# WattmeterV1_1.net
KiCad netlist of a schematic drawn in Altium Designer
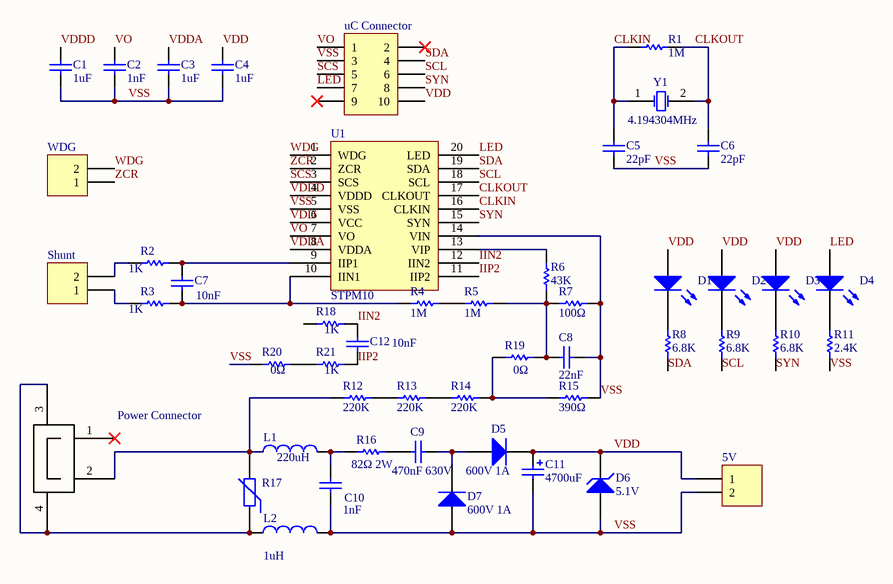
[diagram p0: WattmeterV1.1.SchDoc]

(export (version "E")
  (design (tool "Eeschema 10.0.6"))
  (components
    (comp (ref "5V")
      (value "Header 2")
      (footprint "Female header 2x1")
      (description "Header, 2-Pin")
      (fields (field (name "PUBLISHER") "Altium Limited"))
      (libsource (lib "") (part "Header 2_1"))
    )
    (comp (ref "C1")
      (value "1uF")
      (footprint "Cap SMD 0603")
      (description "Capacitor")
      (fields (field (name "Comment") "Cap") (field (name "PUBLISHER") "Altium Limited"))
      (libsource (lib "Miscellaneous Devices") (part "Cap"))
    )
    (comp (ref "C2")
      (value "1nF")
      (footprint "Cap SMD 0603")
      (description "Capacitor")
      (fields (field (name "Comment") "Cap") (field (name "PUBLISHER") "Altium Limited"))
      (libsource (lib "Miscellaneous Devices") (part "Cap"))
    )
    (comp (ref "C3")
      (value "1uF")
      (footprint "Cap SMD 0603")
      (description "Capacitor")
      (fields (field (name "Comment") "Cap") (field (name "PUBLISHER") "Altium Limited"))
      (libsource (lib "Miscellaneous Devices") (part "Cap"))
    )
    (comp (ref "C4")
      (value "1uF")
      (footprint "Cap SMD 0603")
      (description "Capacitor")
      (fields (field (name "Comment") "Cap") (field (name "PUBLISHER") "Altium Limited"))
      (libsource (lib "Miscellaneous Devices") (part "Cap"))
    )
    (comp (ref "C5")
      (value "22pF")
      (footprint "Cap SMD 0603")
      (description "Capacitor")
      (fields (field (name "Comment") "Cap") (field (name "PUBLISHER") "Altium Limited"))
      (libsource (lib "Miscellaneous Devices") (part "Cap"))
    )
    (comp (ref "C6")
      (value "22pF")
      (footprint "Cap SMD 0603")
      (description "Capacitor")
      (fields (field (name "Comment") "Cap") (field (name "PUBLISHER") "Altium Limited"))
      (libsource (lib "Miscellaneous Devices") (part "Cap"))
    )
    (comp (ref "C7")
      (value "10nF")
      (footprint "Cap SMD 0603")
      (description "Capacitor")
      (fields (field (name "Comment") "Cap") (field (name "PUBLISHER") "Altium Limited"))
      (libsource (lib "Miscellaneous Devices") (part "Cap"))
    )
    (comp (ref "C8")
      (value "22nF")
      (footprint "Cap SMD 0603")
      (description "Capacitor")
      (fields (field (name "Comment") "Cap") (field (name "PUBLISHER") "Altium Limited"))
      (libsource (lib "Miscellaneous Devices") (part "Cap"))
    )
    (comp (ref "C9")
      (value "470nF 630V")
      (footprint "Cap Tenta MKP 470nF X2")
      (description "Capacitor")
      (fields (field (name "Comment") "Cap") (field (name "PUBLISHER") "Altium Limited"))
      (libsource (lib "Miscellaneous Devices") (part "Cap"))
    )
    (comp (ref "C10")
      (value "1nF")
      (footprint "Cap SMD 0603")
      (description "Capacitor")
      (fields (field (name "Comment") "Cap") (field (name "PUBLISHER") "Altium Limited"))
      (libsource (lib "Miscellaneous Devices") (part "Cap"))
    )
    (comp (ref "C11")
      (value "4700uF")
      (footprint "Cap Pol")
      (description "Polarized Capacitor (Axial)")
      (fields (field (name "Comment") "Cap Pol2") (field (name "PUBLISHER") "Altium Limited"))
      (libsource (lib "Miscellaneous Devices") (part "Cap Pol2"))
    )
    (comp (ref "C12")
      (value "10nF")
      (footprint "Cap SMD 0603")
      (description "Capacitor")
      (fields (field (name "Comment") "Cap") (field (name "PUBLISHER") "Altium Limited"))
      (libsource (lib "Miscellaneous Devices") (part "Cap"))
    )
    (comp (ref "D1")
      (value "LED1")
      (footprint "LED Green")
      (description "Typical RED GaAs LED")
      (fields (field (name "PUBLISHER") "Altium Limited"))
      (libsource (lib "Miscellaneous Devices") (part "LED1"))
    )
    (comp (ref "D2")
      (value "LED1")
      (footprint "LED Green")
      (description "Typical RED GaAs LED")
      (fields (field (name "PUBLISHER") "Altium Limited"))
      (libsource (lib "Miscellaneous Devices") (part "LED1"))
    )
    (comp (ref "D3")
      (value "LED1")
      (footprint "LED Green")
      (description "Typical RED GaAs LED")
      (fields (field (name "PUBLISHER") "Altium Limited"))
      (libsource (lib "Miscellaneous Devices") (part "LED1"))
    )
    (comp (ref "D4")
      (value "LED1")
      (footprint "LED Green")
      (description "Typical RED GaAs LED")
      (fields (field (name "PUBLISHER") "Altium Limited"))
      (libsource (lib "Miscellaneous Devices") (part "LED1"))
    )
    (comp (ref "D5")
      (value "600V 1A")
      (footprint "Diode SMD")
      (description "High Conductance Fast Diode")
      (fields (field (name "PUBLISHER") "Altium Limited"))
      (libsource (lib "Miscellaneous Devices") (part "Diode 1N4448"))
    )
    (comp (ref "D6")
      (value "5.1V")
      (footprint "Diode SMD")
      (description "Zener Diode")
      (fields (field (name "PUBLISHER") "Altium Limited"))
      (libsource (lib "Miscellaneous Devices") (part "D Zener"))
    )
    (comp (ref "D7")
      (value "600V 1A")
      (footprint "Diode SMD")
      (description "High Conductance Fast Diode")
      (fields (field (name "PUBLISHER") "Altium Limited"))
      (libsource (lib "Miscellaneous Devices") (part "Diode 1N4448"))
    )
    (comp (ref "L1")
      (value "220uH")
      (footprint "Inductor SMD")
      (description "Inductor")
      (fields (field (name "PUBLISHER") "Altium Limited"))
      (libsource (lib "Miscellaneous Devices") (part "Inductor"))
    )
    (comp (ref "L2")
      (value "1uH")
      (footprint "Inductor SMD")
      (description "Inductor")
      (fields (field (name "PUBLISHER") "Altium Limited"))
      (libsource (lib "Miscellaneous Devices") (part "Inductor"))
    )
    (comp (ref "Power Connector")
      (value "Shunt Resistor")
      (footprint "Power Connector+ Shunt")
      (libsource (lib "STMP Lib") (part "Shunt Resistor"))
    )
    (comp (ref "R1")
      (value "1M")
      (footprint "res 0102")
      (description "Resistor")
      (fields (field (name "Comment") "Res1") (field (name "PUBLISHER") "Altium Limited"))
      (libsource (lib "Miscellaneous Devices") (part "Res1"))
    )
    (comp (ref "R2")
      (value "1K")
      (footprint "Res 0102")
      (description "Resistor")
      (fields (field (name "Comment") "Res1") (field (name "PUBLISHER") "Altium Limited"))
      (libsource (lib "Miscellaneous Devices") (part "Res1"))
    )
    (comp (ref "R3")
      (value "1K")
      (footprint "Res 0102")
      (description "Resistor")
      (fields (field (name "Comment") "Res1") (field (name "PUBLISHER") "Altium Limited"))
      (libsource (lib "Miscellaneous Devices") (part "Res1"))
    )
    (comp (ref "R4")
      (value "1M")
      (footprint "res 0102")
      (description "Resistor")
      (fields (field (name "Comment") "Res1") (field (name "PUBLISHER") "Altium Limited"))
      (libsource (lib "Miscellaneous Devices") (part "Res1"))
    )
    (comp (ref "R5")
      (value "1M")
      (footprint "res 0102")
      (description "Resistor")
      (fields (field (name "Comment") "Res1") (field (name "PUBLISHER") "Altium Limited"))
      (libsource (lib "Miscellaneous Devices") (part "Res1"))
    )
    (comp (ref "R6")
      (value "43K")
      (footprint "res 0102")
      (description "Resistor")
      (fields (field (name "Comment") "Res1") (field (name "PUBLISHER") "Altium Limited"))
      (libsource (lib "Miscellaneous Devices") (part "Res1"))
    )
    (comp (ref "R7")
      (value "100Ω")
      (footprint "res 0102")
      (description "Resistor")
      (fields (field (name "Comment") "Res1") (field (name "PUBLISHER") "Altium Limited"))
      (libsource (lib "Miscellaneous Devices") (part "Res1"))
    )
    (comp (ref "R8")
      (value "6.8K")
      (footprint "RES SMD 0603")
      (description "Resistor")
      (fields (field (name "Comment") "Res1") (field (name "PUBLISHER") "Altium Limited"))
      (libsource (lib "Miscellaneous Devices") (part "Res1"))
    )
    (comp (ref "R9")
      (value "6.8K")
      (footprint "RES SMD 0603")
      (description "Resistor")
      (fields (field (name "Comment") "Res1") (field (name "PUBLISHER") "Altium Limited"))
      (libsource (lib "Miscellaneous Devices") (part "Res1"))
    )
    (comp (ref "R10")
      (value "6.8K")
      (footprint "RES SMD 0603")
      (description "Resistor")
      (fields (field (name "Comment") "Res1") (field (name "PUBLISHER") "Altium Limited"))
      (libsource (lib "Miscellaneous Devices") (part "Res1"))
    )
    (comp (ref "R11")
      (value "2.4K")
      (footprint "RES SMD 0603")
      (description "Resistor")
      (fields (field (name "Comment") "Res1") (field (name "PUBLISHER") "Altium Limited"))
      (libsource (lib "Miscellaneous Devices") (part "Res1"))
    )
    (comp (ref "R12")
      (value "220K")
      (footprint "Res Vertical")
      (description "Resistor")
      (fields (field (name "Comment") "Res1") (field (name "PUBLISHER") "Altium Limited"))
      (libsource (lib "Miscellaneous Devices") (part "Res1"))
    )
    (comp (ref "R13")
      (value "220K")
      (footprint "Res Vertical")
      (description "Resistor")
      (fields (field (name "Comment") "Res1") (field (name "PUBLISHER") "Altium Limited"))
      (libsource (lib "Miscellaneous Devices") (part "Res1"))
    )
    (comp (ref "R14")
      (value "220K")
      (footprint "Res Vertical")
      (description "Resistor")
      (fields (field (name "Comment") "Res1") (field (name "PUBLISHER") "Altium Limited"))
      (libsource (lib "Miscellaneous Devices") (part "Res1"))
    )
    (comp (ref "R15")
      (value "390Ω")
      (footprint "Res 0102")
      (description "Resistor")
      (fields (field (name "Comment") "Res1") (field (name "PUBLISHER") "Altium Limited"))
      (libsource (lib "Miscellaneous Devices") (part "Res1"))
    )
    (comp (ref "R16")
      (value "82Ω 2W")
      (footprint "Res 0.7in")
      (description "Resistor")
      (fields (field (name "Comment") "Res1") (field (name "PUBLISHER") "Altium Limited"))
      (libsource (lib "Miscellaneous Devices") (part "Res1"))
    )
    (comp (ref "R17")
      (value "Res Varistor")
      (footprint "Varistor")
      (description "Varistor (Voltage-Sensitive Resistor)")
      (fields (field (name "PUBLISHER") "Altium Limited"))
      (libsource (lib "Miscellaneous Devices") (part "Res Varistor"))
    )
    (comp (ref "R18")
      (value "1K")
      (footprint "Res SMD 0102")
      (description "Resistor")
      (fields (field (name "Comment") "Res1") (field (name "PUBLISHER") "Altium Limited"))
      (libsource (lib "Miscellaneous Devices") (part "Res1"))
    )
    (comp (ref "R19")
      (value "0Ω")
      (footprint "RES SMD 0603")
      (description "Resistor")
      (fields (field (name "Comment") "Res1") (field (name "PUBLISHER") "Altium Limited"))
      (libsource (lib "Miscellaneous Devices") (part "Res1"))
    )
    (comp (ref "R20")
      (value "0Ω")
      (footprint "RES SMD 0603")
      (description "Resistor")
      (fields (field (name "Comment") "Res1") (field (name "PUBLISHER") "Altium Limited"))
      (libsource (lib "Miscellaneous Devices") (part "Res1"))
    )
    (comp (ref "R21")
      (value "1K")
      (footprint "Res SMD 0102")
      (description "Resistor")
      (fields (field (name "Comment") "Res1") (field (name "PUBLISHER") "Altium Limited"))
      (libsource (lib "Miscellaneous Devices") (part "Res1"))
    )
    (comp (ref "Shunt")
      (value "Header 2")
      (footprint "HDR1X2")
      (description "Header, 2-Pin")
      (fields (field (name "PUBLISHER") "Altium Limited"))
      (libsource (lib "Miscellaneous Connectors") (part "Header 2"))
    )
    (comp (ref "U1") (value "STPM10") (footprint "STPM10") (libsource (lib "STMP Lib") (part "STPM10")))
    (comp (ref "uC Connector")
      (value "Header 5X2")
      (footprint "Male Header 2x5")
      (description "Header, 5-Pin, Dual row")
      (fields (field (name "PUBLISHER") "Altium Limited"))
      (libsource (lib "Miscellaneous Connectors") (part "Header 5X2"))
    )
    (comp (ref "WDG")
      (value "Header 2")
      (footprint "Female header 2x1")
      (description "Header, 2-Pin")
      (fields (field (name "PUBLISHER") "Altium Limited"))
      (libsource (lib "Miscellaneous Connectors") (part "Header 2"))
    )
    (comp (ref "Y1")
      (value "4.194304MHz")
      (footprint "Xtal")
      (description "Crystal Oscillator")
      (fields (field (name "PUBLISHER") "Altium Limited"))
      (libsource (lib "Miscellaneous Devices") (part "XTAL"))
    )
  )
  (nets
    (net (code "1") (name "/CLKIN") (class "Default")
      (node (ref "C5") (pin "2") (pinfunction "2_2") (pintype "passive"))
      (node (ref "R1") (pin "1") (pinfunction "1_1") (pintype "passive"))
      (node (ref "U1") (pin "16") (pinfunction "CLKIN_16") (pintype "passive"))
      (node (ref "Y1") (pin "1") (pinfunction "OSC1_1") (pintype "passive"))
    )
    (net (code "2") (name "/CLKOUT") (class "Default")
      (node (ref "C6") (pin "2") (pinfunction "2_2") (pintype "passive"))
      (node (ref "R1") (pin "2") (pinfunction "2_2") (pintype "passive"))
      (node (ref "U1") (pin "17") (pinfunction "CLKOUT_17") (pintype "passive"))
      (node (ref "Y1") (pin "2") (pinfunction "OSC2_2") (pintype "passive"))
    )
    (net (code "3") (name "/IIN2") (class "Default")
      (node (ref "C12") (pin "2") (pinfunction "2_2") (pintype "passive"))
      (node (ref "R18") (pin "2") (pinfunction "2_2") (pintype "passive"))
      (node (ref "U1") (pin "12") (pinfunction "IIN2_12") (pintype "passive"))
    )
    (net (code "4") (name "/IIP2") (class "Default")
      (node (ref "C12") (pin "1") (pinfunction "1_1") (pintype "passive"))
      (node (ref "R21") (pin "2") (pinfunction "2_2") (pintype "passive"))
      (node (ref "U1") (pin "11") (pinfunction "IIP2_11") (pintype "passive"))
    )
    (net (code "5") (name "/LED") (class "Default")
      (node (ref "D4") (pin "1") (pinfunction "A_1") (pintype "passive"))
      (node (ref "U1") (pin "20") (pinfunction "LED_20") (pintype "passive"))
      (node (ref "uC Connector") (pin "7") (pinfunction "7_7") (pintype "passive"))
    )
    (net (code "6") (name "/SCL") (class "Default")
      (node (ref "R9") (pin "1") (pinfunction "1_1") (pintype "passive"))
      (node (ref "U1") (pin "18") (pinfunction "SCL_18") (pintype "passive"))
      (node (ref "uC Connector") (pin "6") (pinfunction "6_6") (pintype "passive"))
    )
    (net (code "7") (name "/SCS") (class "Default")
      (node (ref "U1") (pin "3") (pinfunction "SCS_3") (pintype "passive"))
      (node (ref "uC Connector") (pin "5") (pinfunction "5_5") (pintype "passive"))
    )
    (net (code "8") (name "/SDA") (class "Default")
      (node (ref "R8") (pin "1") (pinfunction "1_1") (pintype "passive"))
      (node (ref "U1") (pin "19") (pinfunction "SDA_19") (pintype "passive"))
      (node (ref "uC Connector") (pin "4") (pinfunction "4_4") (pintype "passive"))
    )
    (net (code "9") (name "/SYN") (class "Default")
      (node (ref "R10") (pin "1") (pinfunction "1_1") (pintype "passive"))
      (node (ref "U1") (pin "15") (pinfunction "SYN_15") (pintype "passive"))
      (node (ref "uC Connector") (pin "8") (pinfunction "8_8") (pintype "passive"))
    )
    (net (code "10") (name "/VDD") (class "Default")
      (node (ref "5V") (pin "1") (pinfunction "1_1") (pintype "passive"))
      (node (ref "C11") (pin "1") (pinfunction "1_1") (pintype "passive"))
      (node (ref "C4") (pin "2") (pinfunction "2_2") (pintype "passive"))
      (node (ref "D1") (pin "1") (pinfunction "A_1") (pintype "passive"))
      (node (ref "D2") (pin "1") (pinfunction "A_1") (pintype "passive"))
      (node (ref "D3") (pin "1") (pinfunction "A_1") (pintype "passive"))
      (node (ref "D5") (pin "2") (pinfunction "K_2") (pintype "passive"))
      (node (ref "D6") (pin "2") (pinfunction "K_2") (pintype "passive"))
      (node (ref "U1") (pin "6") (pinfunction "VCC_6") (pintype "passive"))
      (node (ref "uC Connector") (pin "10") (pinfunction "10_10") (pintype "passive"))
    )
    (net (code "11") (name "/VDDA") (class "Default")
      (node (ref "C3") (pin "2") (pinfunction "2_2") (pintype "passive"))
      (node (ref "U1") (pin "8") (pinfunction "VDDA_8") (pintype "passive"))
    )
    (net (code "12") (name "/VDDD") (class "Default")
      (node (ref "C1") (pin "2") (pinfunction "2_2") (pintype "passive"))
      (node (ref "U1") (pin "4") (pinfunction "VDDD_4") (pintype "passive"))
    )
    (net (code "13") (name "/VO") (class "Default")
      (node (ref "C2") (pin "2") (pinfunction "2_2") (pintype "passive"))
      (node (ref "U1") (pin "7") (pinfunction "VO_7") (pintype "passive"))
      (node (ref "uC Connector") (pin "1") (pinfunction "1_1") (pintype "passive"))
    )
    (net (code "14") (name "/VSS") (class "Default")
      (node (ref "5V") (pin "2") (pinfunction "2_2") (pintype "passive"))
      (node (ref "C1") (pin "1") (pinfunction "1_1") (pintype "passive"))
      (node (ref "C10") (pin "1") (pinfunction "1_1") (pintype "passive"))
      (node (ref "C11") (pin "2") (pinfunction "2_2") (pintype "passive"))
      (node (ref "C2") (pin "1") (pinfunction "1_1") (pintype "passive"))
      (node (ref "C3") (pin "1") (pinfunction "1_1") (pintype "passive"))
      (node (ref "C4") (pin "1") (pinfunction "1_1") (pintype "passive"))
      (node (ref "C5") (pin "1") (pinfunction "1_1") (pintype "passive"))
      (node (ref "C6") (pin "1") (pinfunction "1_1") (pintype "passive"))
      (node (ref "C8") (pin "2") (pinfunction "2_2") (pintype "passive"))
      (node (ref "D6") (pin "1") (pinfunction "A_1") (pintype "passive"))
      (node (ref "D7") (pin "1") (pinfunction "A_1") (pintype "passive"))
      (node (ref "L2") (pin "2") (pinfunction "2_2") (pintype "passive"))
      (node (ref "R11") (pin "1") (pinfunction "1_1") (pintype "passive"))
      (node (ref "R15") (pin "2") (pinfunction "2_2") (pintype "passive"))
      (node (ref "R20") (pin "1") (pinfunction "1_1") (pintype "passive"))
      (node (ref "R7") (pin "2") (pinfunction "2_2") (pintype "passive"))
      (node (ref "U1") (pin "14") (pinfunction "VIN_14") (pintype "passive"))
      (node (ref "U1") (pin "5") (pinfunction "VSS_5") (pintype "passive"))
      (node (ref "uC Connector") (pin "3") (pinfunction "3_3") (pintype "passive"))
    )
    (net (code "15") (name "/WDG") (class "Default")
      (node (ref "U1") (pin "1") (pinfunction "WDG_1") (pintype "passive"))
      (node (ref "WDG") (pin "2") (pinfunction "2_2") (pintype "passive"))
    )
    (net (code "16") (name "/ZCR") (class "Default")
      (node (ref "U1") (pin "2") (pinfunction "ZCR_2") (pintype "passive"))
      (node (ref "WDG") (pin "1") (pinfunction "1_1") (pintype "passive"))
    )
    (net (code "17") (name "Net-(C8-Pad1)") (class "Default")
      (node (ref "C8") (pin "1") (pinfunction "1_1") (pintype "passive"))
      (node (ref "R19") (pin "2") (pinfunction "2_2") (pintype "passive"))
      (node (ref "R5") (pin "2") (pinfunction "2_2") (pintype "passive"))
      (node (ref "R6") (pin "1") (pinfunction "1_1") (pintype "passive"))
      (node (ref "R7") (pin "1") (pinfunction "1_1") (pintype "passive"))
    )
    (net (code "18") (name "Net-(C9-Pad2)") (class "Default")
      (node (ref "C9") (pin "2") (pinfunction "2_2") (pintype "passive"))
      (node (ref "R16") (pin "2") (pinfunction "2_2") (pintype "passive"))
    )
    (net (code "19") (name "Net-(C10-Pad2)") (class "Default")
      (node (ref "C10") (pin "2") (pinfunction "2_2") (pintype "passive"))
      (node (ref "L1") (pin "2") (pinfunction "2_2") (pintype "passive"))
      (node (ref "R16") (pin "1") (pinfunction "1_1") (pintype "passive"))
    )
    (net (code "20") (name "Net-(D1-K)") (class "Default")
      (node (ref "D1") (pin "2") (pinfunction "K_2") (pintype "passive"))
      (node (ref "R8") (pin "2") (pinfunction "2_2") (pintype "passive"))
    )
    (net (code "21") (name "Net-(D2-K)") (class "Default")
      (node (ref "D2") (pin "2") (pinfunction "K_2") (pintype "passive"))
      (node (ref "R9") (pin "2") (pinfunction "2_2") (pintype "passive"))
    )
    (net (code "22") (name "Net-(D3-K)") (class "Default")
      (node (ref "D3") (pin "2") (pinfunction "K_2") (pintype "passive"))
      (node (ref "R10") (pin "2") (pinfunction "2_2") (pintype "passive"))
    )
    (net (code "23") (name "Net-(D4-K)") (class "Default")
      (node (ref "D4") (pin "2") (pinfunction "K_2") (pintype "passive"))
      (node (ref "R11") (pin "2") (pinfunction "2_2") (pintype "passive"))
    )
    (net (code "24") (name "Net-(D5-A)") (class "Default")
      (node (ref "C9") (pin "1") (pinfunction "1_1") (pintype "passive"))
      (node (ref "D5") (pin "1") (pinfunction "A_1") (pintype "passive"))
      (node (ref "D7") (pin "2") (pinfunction "K_2") (pintype "passive"))
    )
    (net (code "25") (name "Net-(L1-Pad1)") (class "Default")
      (node (ref "L1") (pin "1") (pinfunction "1_1") (pintype "passive"))
      (node (ref "Power Connector") (pin "2") (pintype "passive"))
      (node (ref "R12") (pin "1") (pinfunction "1_1") (pintype "passive"))
      (node (ref "R17") (pin "2") (pinfunction "2_2") (pintype "passive"))
    )
    (net (code "26") (name "Net-(L2-Pad1)") (class "Default")
      (node (ref "L2") (pin "1") (pinfunction "1_1") (pintype "passive"))
      (node (ref "Power Connector") (pin "3") (pintype "passive"))
      (node (ref "Power Connector") (pin "4") (pintype "passive"))
      (node (ref "R17") (pin "1") (pinfunction "1_1") (pintype "passive"))
    )
    (net (code "27") (name "Net-(R2-Pad1)") (class "Default")
      (node (ref "R2") (pin "1") (pinfunction "1_1") (pintype "passive"))
      (node (ref "Shunt") (pin "2") (pinfunction "2_2") (pintype "passive"))
    )
    (net (code "28") (name "Net-(R3-Pad1)") (class "Default")
      (node (ref "R3") (pin "1") (pinfunction "1_1") (pintype "passive"))
      (node (ref "Shunt") (pin "1") (pinfunction "1_1") (pintype "passive"))
    )
    (net (code "29") (name "Net-(R4-Pad2)") (class "Default")
      (node (ref "R4") (pin "2") (pinfunction "2_2") (pintype "passive"))
      (node (ref "R5") (pin "1") (pinfunction "1_1") (pintype "passive"))
    )
    (net (code "30") (name "Net-(R12-Pad2)") (class "Default")
      (node (ref "R12") (pin "2") (pinfunction "2_2") (pintype "passive"))
      (node (ref "R13") (pin "1") (pinfunction "1_1") (pintype "passive"))
    )
    (net (code "31") (name "Net-(R13-Pad2)") (class "Default")
      (node (ref "R13") (pin "2") (pinfunction "2_2") (pintype "passive"))
      (node (ref "R14") (pin "1") (pinfunction "1_1") (pintype "passive"))
    )
    (net (code "32") (name "Net-(R14-Pad2)") (class "Default")
      (node (ref "R14") (pin "2") (pinfunction "2_2") (pintype "passive"))
      (node (ref "R15") (pin "1") (pinfunction "1_1") (pintype "passive"))
      (node (ref "R19") (pin "1") (pinfunction "1_1") (pintype "passive"))
    )
    (net (code "33") (name "Net-(R20-Pad2)") (class "Default")
      (node (ref "R20") (pin "2") (pinfunction "2_2") (pintype "passive"))
      (node (ref "R21") (pin "1") (pinfunction "1_1") (pintype "passive"))
    )
    (net (code "34") (name "Net-(U1-IIN1)") (class "Default")
      (node (ref "C7") (pin "1") (pinfunction "1_1") (pintype "passive"))
      (node (ref "R3") (pin "2") (pinfunction "2_2") (pintype "passive"))
      (node (ref "R4") (pin "1") (pinfunction "1_1") (pintype "passive"))
      (node (ref "U1") (pin "10") (pinfunction "IIN1_10") (pintype "passive"))
    )
    (net (code "35") (name "Net-(U1-IIP1)") (class "Default")
      (node (ref "C7") (pin "2") (pinfunction "2_2") (pintype "passive"))
      (node (ref "R2") (pin "2") (pinfunction "2_2") (pintype "passive"))
      (node (ref "U1") (pin "9") (pinfunction "IIP1_9") (pintype "passive"))
    )
    (net (code "36") (name "Net-(U1-VIP)") (class "Default")
      (node (ref "R6") (pin "2") (pinfunction "2_2") (pintype "passive"))
      (node (ref "U1") (pin "13") (pinfunction "VIP_13") (pintype "passive"))
    )
    (net (code "37") (name "unconnected-(Power Connector-Pad1)") (class "Default")
      (node (ref "Power Connector") (pin "1") (pintype "passive+no_connect"))
    )
    (net (code "38") (name "unconnected-(R18-Pad1)") (class "Default")
      (node (ref "R18") (pin "1") (pinfunction "1_1") (pintype "passive"))
    )
    (net (code "39") (name "unconnected-(uC Connector-Pad2)") (class "Default")
      (node (ref "uC Connector") (pin "2") (pinfunction "2_2") (pintype "passive+no_connect"))
    )
    (net (code "40") (name "unconnected-(uC Connector-Pad9)") (class "Default")
      (node (ref "uC Connector") (pin "9") (pinfunction "9_9") (pintype "passive+no_connect"))
    )
  )
)
